# Artix7_SRAM.net
KiCad netlist of a schematic drawn in Altium Designer
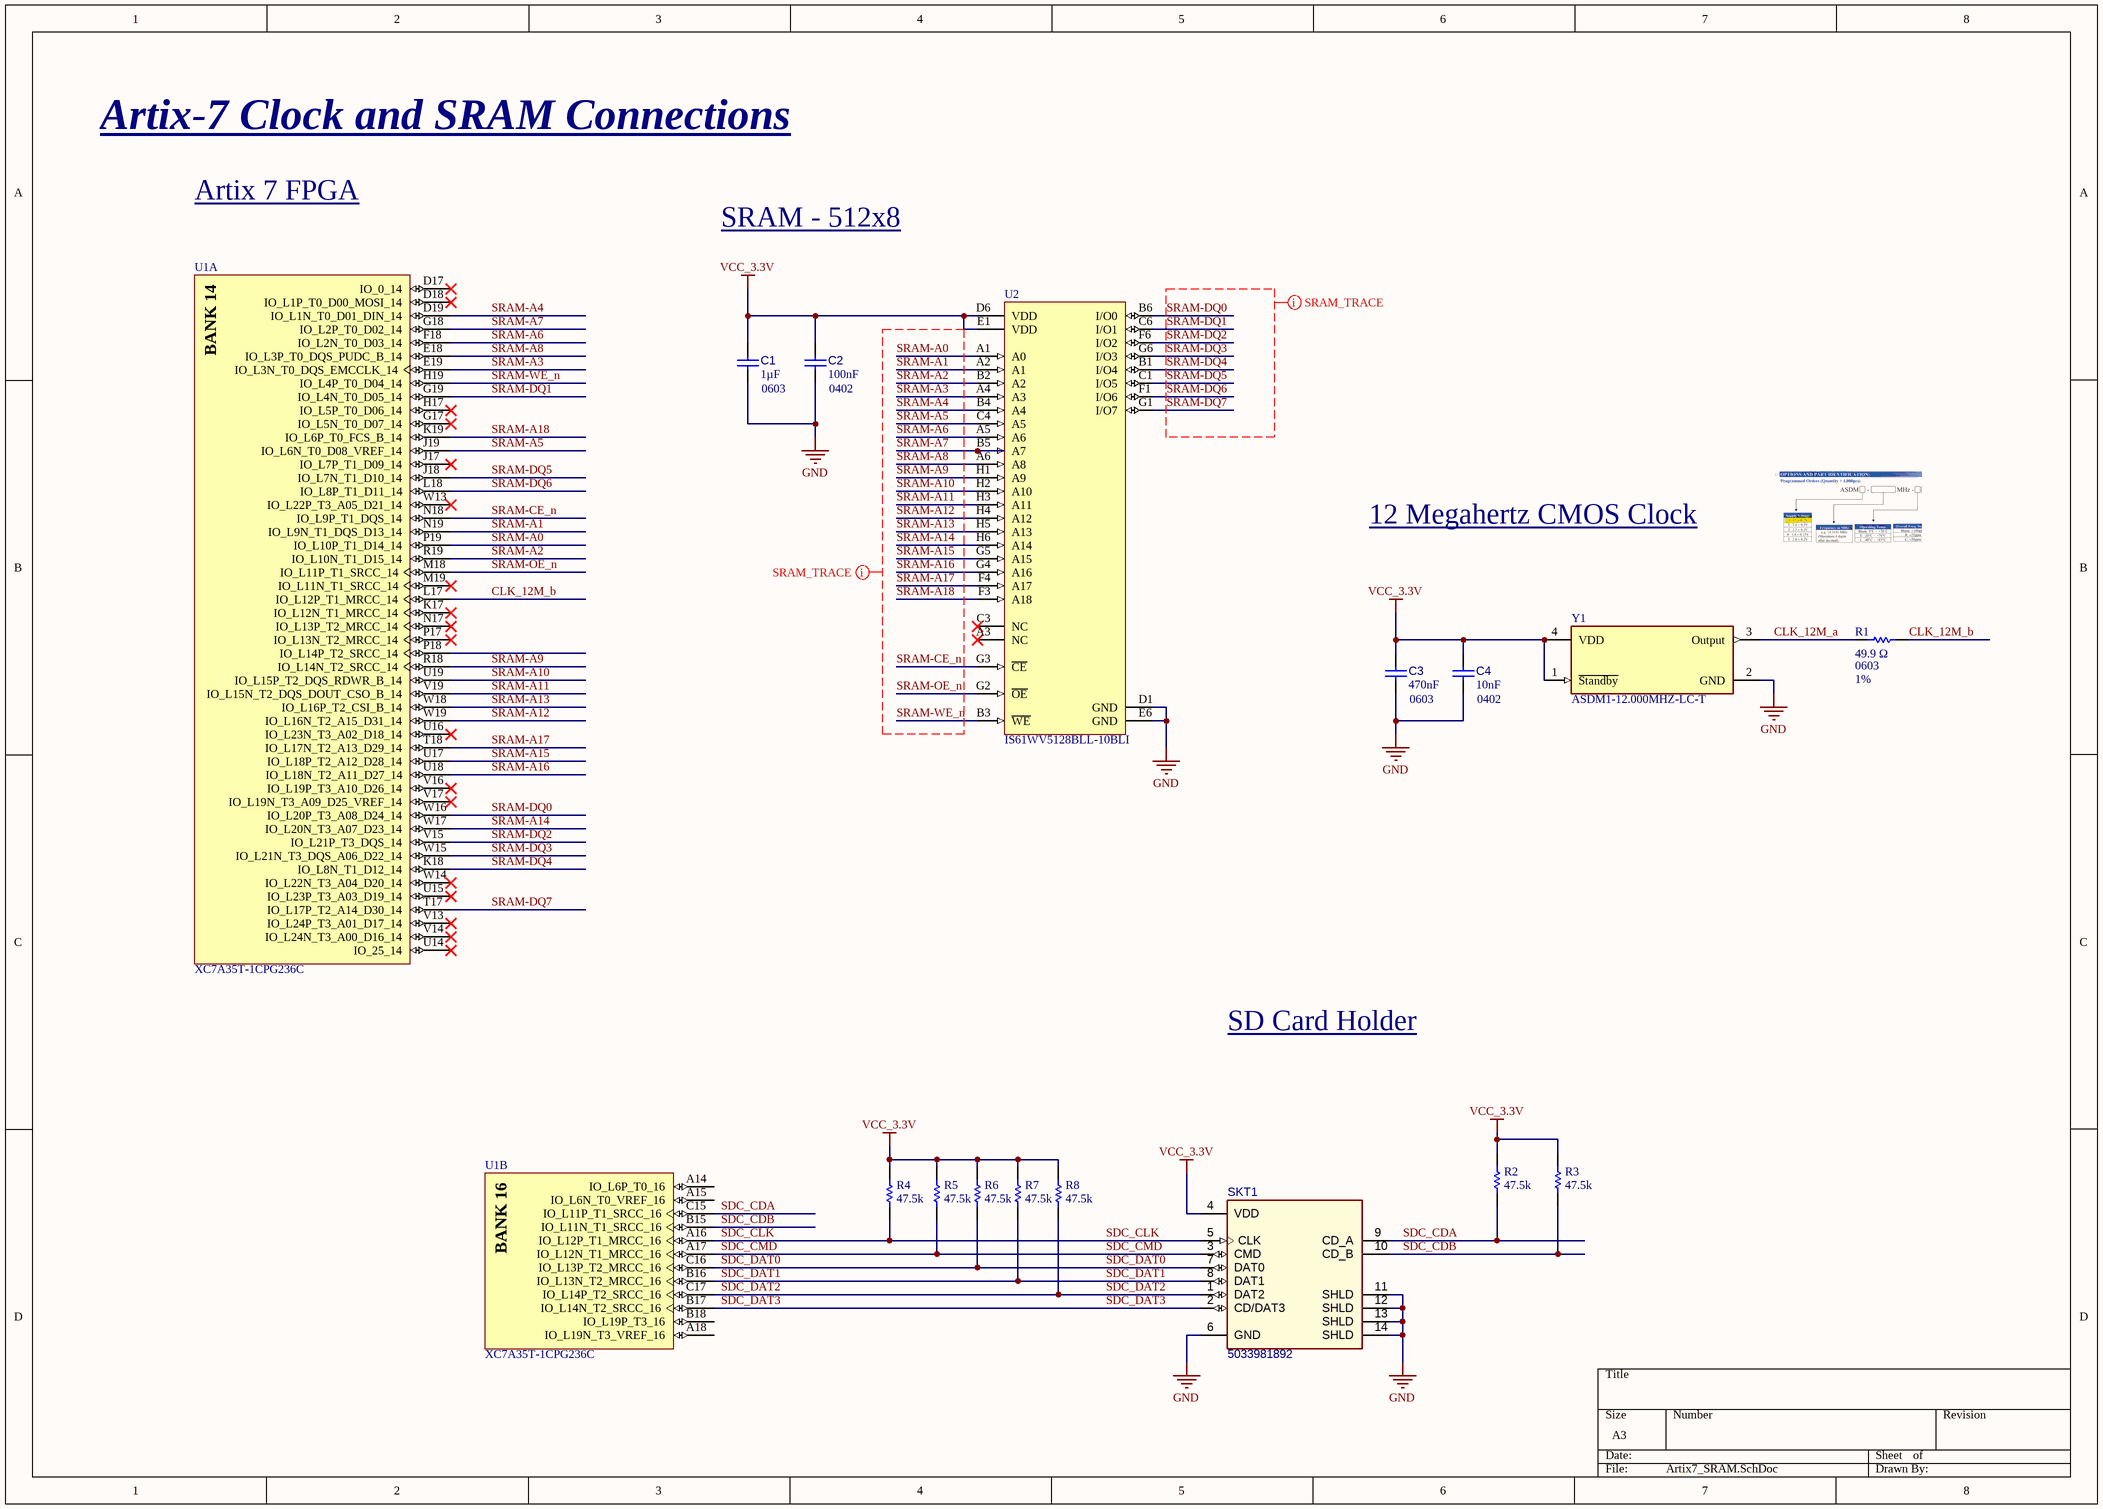
[diagram p0: Artix7_SRAM.SchDoc]

(export (version "E")
  (design (tool "Eeschema 10.0.6"))
  (components
    (comp (ref "C1")
      (value "1µF")
      (footprint "CAPC0603(1608)100_L")
      (description "Chip Capacitor, 1µF +/-0.1%, 25V, 0603, Thickness 1 mm")
      (fields
        (field (name "TOLERANCE") "20%")
        (field (name "CASE/PACKAGE") "0603")
        (field (name "Comment") "Capacitor 1µF +/-0.1% 25V 0603")
      )
      (libsource (lib "Personal Workspace") (part "CAP-NP-2"))
    )
    (comp (ref "C2")
      (value "100nF")
      (footprint "CAPC0402(1005)60_L")
      (description "Chip Capacitor, 100nF +/-20%, 25V, 0402, Thickness 0.6 mm")
      (fields
        (field (name "CASE/PACKAGE") "0402")
        (field (name "TOLERANCE") "10%")
        (field (name "Comment") "Capacitor 100nF +/-20% 25V 0402")
      )
      (libsource (lib "Personal Workspace") (part "CAP-NP-2"))
    )
    (comp (ref "C3")
      (value "470nF")
      (footprint "CAPC0603(1608)100_L")
      (description "Chip Capacitor, 470nF +/-20%, 25V, 0603, Thickness 1 mm")
      (fields
        (field (name "TOLERANCE") "10%")
        (field (name "CASE/PACKAGE") "0603")
        (field (name "Comment") "Capacitor 470nF +/-20% 25V 0603")
      )
      (libsource (lib "Personal Workspace") (part "CAP-NP-2"))
    )
    (comp (ref "C4")
      (value "10nF")
      (footprint "CAPC0402(1005)60_L")
      (description "Chip Capacitor, 10nF +/-20%, 50V, 0402, Thickness 0.6 mm")
      (fields
        (field (name "CASE/PACKAGE") "0402")
        (field (name "TOLERANCE") "5%")
        (field (name "Comment") "Capacitor 10nF +/-20% 50V 0402")
      )
      (libsource (lib "Personal Workspace") (part "CAP-NP-2"))
    )
    (comp (ref "R1")
      (value "49.9 Ω")
      (footprint "RESC1608X55X25NL10T15")
      (fields
        (field (name "PACKAGEREFERENCE") "0603")
        (field (name "TOLERANCE") "1%")
        (field (name "Comment") "RC0603FR-0749R9L")
      )
      (libsource (lib "Altium Content Vault") (part "RES-2"))
    )
    (comp (ref "R2")
      (value "47.5k")
      (footprint "RESC0402(1005)_L")
      (description "47K5 0.063W 1% 0402 (1005 Metric)  SMD")
      (fields (field (name "TOLERANCE") "1%") (field (name "POWER") "63mW"))
      (libsource (lib "Personal Workspace") (part "RES-2"))
    )
    (comp (ref "R3")
      (value "47.5k")
      (footprint "RESC0402(1005)_L")
      (description "47K5 0.063W 1% 0402 (1005 Metric)  SMD")
      (fields (field (name "TOLERANCE") "1%") (field (name "POWER") "63mW"))
      (libsource (lib "Personal Workspace") (part "RES-2"))
    )
    (comp (ref "R4")
      (value "47.5k")
      (footprint "RESC0402(1005)_L")
      (description "47K5 0.063W 1% 0402 (1005 Metric)  SMD")
      (fields (field (name "TOLERANCE") "1%") (field (name "POWER") "63mW"))
      (libsource (lib "Personal Workspace") (part "RES-2"))
    )
    (comp (ref "R5")
      (value "47.5k")
      (footprint "RESC0402(1005)_L")
      (description "47K5 0.063W 1% 0402 (1005 Metric)  SMD")
      (fields (field (name "TOLERANCE") "1%") (field (name "POWER") "63mW"))
      (libsource (lib "Personal Workspace") (part "RES-2"))
    )
    (comp (ref "R6")
      (value "47.5k")
      (footprint "RESC0402(1005)_L")
      (description "47K5 0.063W 1% 0402 (1005 Metric)  SMD")
      (fields (field (name "TOLERANCE") "1%") (field (name "POWER") "63mW"))
      (libsource (lib "Personal Workspace") (part "RES-2"))
    )
    (comp (ref "R7")
      (value "47.5k")
      (footprint "RESC0402(1005)_L")
      (description "47K5 0.063W 1% 0402 (1005 Metric)  SMD")
      (fields (field (name "TOLERANCE") "1%") (field (name "POWER") "63mW"))
      (libsource (lib "Personal Workspace") (part "RES-2"))
    )
    (comp (ref "R8")
      (value "47.5k")
      (footprint "RESC0402(1005)_L")
      (description "47K5 0.063W 1% 0402 (1005 Metric)  SMD")
      (fields (field (name "TOLERANCE") "1%") (field (name "POWER") "63mW"))
      (libsource (lib "Personal Workspace") (part "RES-2"))
    )
    (comp (ref "SKT1")
      (value "5033981892")
      (footprint "MOLX-5033981892_V")
      (libsource (lib "Personal Workspace") (part "CMP-00040-6"))
    )
    (comp (ref "U1")
      (value "XC7A35T-1CPG236C")
      (footprint "CPG236")
      (description "Artix-7 FPGA, 106 User I/Os, 2 GTP, 238-Ball BGA, Speed Grade 1, Commercial Grade, Pb-Free")
      (fields (field (name "MANUFACTURER") "Xilinx"))
      (libsource (lib "") (part "XLNX-XC7A35T-CPG236_1"))
    )
    (comp (ref "U2")
      (value "IS61WV5128BLL-10BLI")
      (footprint "FP-IS61WV5128BLL-10BLI-IPC_A")
      (libsource (lib "Altium Content Vault") (part "7547a2fdd47ed936ab9e56fa022b1f9"))
    )
    (comp (ref "Y1")
      (value "ASDM1-12.000MHZ-LC-T")
      (footprint "FP-ASDM-ASDMB-MFG")
      (description "MEMS Oscillator 12MHz ±50ppm LVCMOS 3.3V SMD 2.5x2mm")
      (libsource (lib "Altium Content Vault") (part "d1c68ac5f38726358044f3b7e06346c"))
    )
  )
  (nets
    (net (code "1") (name "/CLK_12M_a") (class "Default")
      (node (ref "R1") (pin "1") (pinfunction "1_1") (pintype "passive"))
      (node (ref "Y1") (pin "3") (pinfunction "Output_3") (pintype "output"))
    )
    (net (code "2") (name "/CLK_12M_b") (class "Default")
      (node (ref "R1") (pin "2") (pinfunction "2_2") (pintype "passive"))
      (node (ref "U1") (pin "L17") (pinfunction "IO_L12P_T1_MRCC_14_L17") (pintype "bidirectional"))
    )
    (net (code "3") (name "/SDC_CDA") (class "Default")
      (node (ref "R2") (pin "1") (pinfunction "1_1") (pintype "passive"))
      (node (ref "SKT1") (pin "9") (pinfunction "CD_A_9") (pintype "passive"))
      (node (ref "U1") (pin "C15") (pinfunction "IO_L11P_T1_SRCC_16_C15") (pintype "bidirectional"))
    )
    (net (code "4") (name "/SDC_CDB") (class "Default")
      (node (ref "R3") (pin "1") (pinfunction "1_1") (pintype "passive"))
      (node (ref "SKT1") (pin "10") (pinfunction "CD_B_10") (pintype "passive"))
      (node (ref "U1") (pin "B15") (pinfunction "IO_L11N_T1_SRCC_16_B15") (pintype "bidirectional"))
    )
    (net (code "5") (name "/SDC_CLK") (class "Default")
      (node (ref "R4") (pin "1") (pinfunction "1_1") (pintype "passive"))
      (node (ref "SKT1") (pin "5") (pinfunction "CLK_5") (pintype "input"))
      (node (ref "U1") (pin "A16") (pinfunction "IO_L12P_T1_MRCC_16_A16") (pintype "bidirectional"))
    )
    (net (code "6") (name "/SDC_CMD") (class "Default")
      (node (ref "R5") (pin "1") (pinfunction "1_1") (pintype "passive"))
      (node (ref "SKT1") (pin "3") (pinfunction "CMD_3") (pintype "bidirectional"))
      (node (ref "U1") (pin "A17") (pinfunction "IO_L12N_T1_MRCC_16_A17") (pintype "bidirectional"))
    )
    (net (code "7") (name "/SDC_DAT0") (class "Default")
      (node (ref "R6") (pin "1") (pinfunction "1_1") (pintype "passive"))
      (node (ref "SKT1") (pin "7") (pinfunction "DAT0_7") (pintype "bidirectional"))
      (node (ref "U1") (pin "C16") (pinfunction "IO_L13P_T2_MRCC_16_C16") (pintype "bidirectional"))
    )
    (net (code "8") (name "/SDC_DAT1") (class "Default")
      (node (ref "R7") (pin "1") (pinfunction "1_1") (pintype "passive"))
      (node (ref "SKT1") (pin "8") (pinfunction "DAT1_8") (pintype "bidirectional"))
      (node (ref "U1") (pin "B16") (pinfunction "IO_L13N_T2_MRCC_16_B16") (pintype "bidirectional"))
    )
    (net (code "9") (name "/SDC_DAT2") (class "Default")
      (node (ref "R8") (pin "1") (pinfunction "1_1") (pintype "passive"))
      (node (ref "SKT1") (pin "1") (pinfunction "DAT2_1") (pintype "bidirectional"))
      (node (ref "U1") (pin "C17") (pinfunction "IO_L14P_T2_SRCC_16_C17") (pintype "bidirectional"))
    )
    (net (code "10") (name "/SDC_DAT3") (class "Default")
      (node (ref "SKT1") (pin "2") (pinfunction "CD/DAT3_2") (pintype "bidirectional"))
      (node (ref "U1") (pin "B17") (pinfunction "IO_L14N_T2_SRCC_16_B17") (pintype "bidirectional"))
    )
    (net (code "11") (name "/SRAM-A0") (class "Default")
      (node (ref "U1") (pin "P19") (pinfunction "IO_L10P_T1_D14_14_P19") (pintype "bidirectional"))
      (node (ref "U2") (pin "A1") (pinfunction "A0_A1") (pintype "input"))
    )
    (net (code "12") (name "/SRAM-A1") (class "Default")
      (node (ref "U1") (pin "N19") (pinfunction "IO_L9N_T1_DQS_D13_14_N19") (pintype "bidirectional"))
      (node (ref "U2") (pin "A2") (pinfunction "A1_A2") (pintype "input"))
    )
    (net (code "13") (name "/SRAM-A2") (class "Default")
      (node (ref "U1") (pin "R19") (pinfunction "IO_L10N_T1_D15_14_R19") (pintype "bidirectional"))
      (node (ref "U2") (pin "B2") (pinfunction "A2_B2") (pintype "input"))
    )
    (net (code "14") (name "/SRAM-A3") (class "Default")
      (node (ref "U1") (pin "E19") (pinfunction "IO_L3N_T0_DQS_EMCCLK_14_E19") (pintype "bidirectional"))
      (node (ref "U2") (pin "A4") (pinfunction "A3_A4") (pintype "input"))
    )
    (net (code "15") (name "/SRAM-A4") (class "Default")
      (node (ref "U1") (pin "D19") (pinfunction "IO_L1N_T0_D01_DIN_14_D19") (pintype "bidirectional"))
      (node (ref "U2") (pin "B4") (pinfunction "A4_B4") (pintype "input"))
    )
    (net (code "16") (name "/SRAM-A5") (class "Default")
      (node (ref "U1") (pin "J19") (pinfunction "IO_L6N_T0_D08_VREF_14_J19") (pintype "bidirectional"))
      (node (ref "U2") (pin "C4") (pinfunction "A5_C4") (pintype "input"))
    )
    (net (code "17") (name "/SRAM-A6") (class "Default")
      (node (ref "U1") (pin "F18") (pinfunction "IO_L2N_T0_D03_14_F18") (pintype "bidirectional"))
      (node (ref "U2") (pin "A5") (pinfunction "A6_A5") (pintype "input"))
    )
    (net (code "18") (name "/SRAM-A7") (class "Default")
      (node (ref "U1") (pin "G18") (pinfunction "IO_L2P_T0_D02_14_G18") (pintype "bidirectional"))
      (node (ref "U2") (pin "B5") (pinfunction "A7_B5") (pintype "input"))
    )
    (net (code "19") (name "/SRAM-A8") (class "Default")
      (node (ref "U1") (pin "E18") (pinfunction "IO_L3P_T0_DQS_PUDC_B_14_E18") (pintype "bidirectional"))
      (node (ref "U2") (pin "A6") (pinfunction "A8_A6") (pintype "input"))
    )
    (net (code "20") (name "/SRAM-A9") (class "Default")
      (node (ref "U1") (pin "R18") (pinfunction "IO_L14N_T2_SRCC_14_R18") (pintype "bidirectional"))
      (node (ref "U2") (pin "H1") (pinfunction "A9_H1") (pintype "input"))
    )
    (net (code "21") (name "/SRAM-A10") (class "Default")
      (node (ref "U1") (pin "U19") (pinfunction "IO_L15P_T2_DQS_RDWR_B_14_U19") (pintype "bidirectional"))
      (node (ref "U2") (pin "H2") (pinfunction "A10_H2") (pintype "input"))
    )
    (net (code "22") (name "/SRAM-A11") (class "Default")
      (node (ref "U1") (pin "V19") (pinfunction "IO_L15N_T2_DQS_DOUT_CSO_B_14_V19") (pintype "bidirectional"))
      (node (ref "U2") (pin "H3") (pinfunction "A11_H3") (pintype "input"))
    )
    (net (code "23") (name "/SRAM-A12") (class "Default")
      (node (ref "U1") (pin "W19") (pinfunction "IO_L16N_T2_A15_D31_14_W19") (pintype "bidirectional"))
      (node (ref "U2") (pin "H4") (pinfunction "A12_H4") (pintype "input"))
    )
    (net (code "24") (name "/SRAM-A13") (class "Default")
      (node (ref "U1") (pin "W18") (pinfunction "IO_L16P_T2_CSI_B_14_W18") (pintype "bidirectional"))
      (node (ref "U2") (pin "H5") (pinfunction "A13_H5") (pintype "input"))
    )
    (net (code "25") (name "/SRAM-A14") (class "Default")
      (node (ref "U1") (pin "W17") (pinfunction "IO_L20N_T3_A07_D23_14_W17") (pintype "bidirectional"))
      (node (ref "U2") (pin "H6") (pinfunction "A14_H6") (pintype "input"))
    )
    (net (code "26") (name "/SRAM-A15") (class "Default")
      (node (ref "U1") (pin "U17") (pinfunction "IO_L18P_T2_A12_D28_14_U17") (pintype "bidirectional"))
      (node (ref "U2") (pin "G5") (pinfunction "A15_G5") (pintype "input"))
    )
    (net (code "27") (name "/SRAM-A16") (class "Default")
      (node (ref "U1") (pin "U18") (pinfunction "IO_L18N_T2_A11_D27_14_U18") (pintype "bidirectional"))
      (node (ref "U2") (pin "G4") (pinfunction "A16_G4") (pintype "input"))
    )
    (net (code "28") (name "/SRAM-A17") (class "Default")
      (node (ref "U1") (pin "T18") (pinfunction "IO_L17N_T2_A13_D29_14_T18") (pintype "bidirectional"))
      (node (ref "U2") (pin "F4") (pinfunction "A17_F4") (pintype "input"))
    )
    (net (code "29") (name "/SRAM-A18") (class "Default")
      (node (ref "U1") (pin "K19") (pinfunction "IO_L6P_T0_FCS_B_14_K19") (pintype "bidirectional"))
      (node (ref "U2") (pin "F3") (pinfunction "A18_F3") (pintype "input"))
    )
    (net (code "30") (name "/SRAM-CE_n") (class "Default")
      (node (ref "U1") (pin "N18") (pinfunction "IO_L9P_T1_DQS_14_N18") (pintype "bidirectional"))
      (node (ref "U2") (pin "G3") (pinfunction "~{CE}_G3") (pintype "input"))
    )
    (net (code "31") (name "/SRAM-DQ0") (class "Default")
      (node (ref "U1") (pin "W16") (pinfunction "IO_L20P_T3_A08_D24_14_W16") (pintype "bidirectional"))
      (node (ref "U2") (pin "B6") (pinfunction "I/O0_B6") (pintype "bidirectional"))
    )
    (net (code "32") (name "/SRAM-DQ1") (class "Default")
      (node (ref "U1") (pin "G19") (pinfunction "IO_L4N_T0_D05_14_G19") (pintype "bidirectional"))
      (node (ref "U2") (pin "C6") (pinfunction "I/O1_C6") (pintype "bidirectional"))
    )
    (net (code "33") (name "/SRAM-DQ2") (class "Default")
      (node (ref "U1") (pin "V15") (pinfunction "IO_L21P_T3_DQS_14_V15") (pintype "bidirectional"))
      (node (ref "U2") (pin "F6") (pinfunction "I/O2_F6") (pintype "bidirectional"))
    )
    (net (code "34") (name "/SRAM-DQ3") (class "Default")
      (node (ref "U1") (pin "W15") (pinfunction "IO_L21N_T3_DQS_A06_D22_14_W15") (pintype "bidirectional"))
      (node (ref "U2") (pin "G6") (pinfunction "I/O3_G6") (pintype "bidirectional"))
    )
    (net (code "35") (name "/SRAM-DQ4") (class "Default")
      (node (ref "U1") (pin "K18") (pinfunction "IO_L8N_T1_D12_14_K18") (pintype "bidirectional"))
      (node (ref "U2") (pin "B1") (pinfunction "I/O4_B1") (pintype "bidirectional"))
    )
    (net (code "36") (name "/SRAM-DQ5") (class "Default")
      (node (ref "U1") (pin "J18") (pinfunction "IO_L7N_T1_D10_14_J18") (pintype "bidirectional"))
      (node (ref "U2") (pin "C1") (pinfunction "I/O5_C1") (pintype "bidirectional"))
    )
    (net (code "37") (name "/SRAM-DQ6") (class "Default")
      (node (ref "U1") (pin "L18") (pinfunction "IO_L8P_T1_D11_14_L18") (pintype "bidirectional"))
      (node (ref "U2") (pin "F1") (pinfunction "I/O6_F1") (pintype "bidirectional"))
    )
    (net (code "38") (name "/SRAM-DQ7") (class "Default")
      (node (ref "U1") (pin "T17") (pinfunction "IO_L17P_T2_A14_D30_14_T17") (pintype "bidirectional"))
      (node (ref "U2") (pin "G1") (pinfunction "I/O7_G1") (pintype "bidirectional"))
    )
    (net (code "39") (name "/SRAM-OE_n") (class "Default")
      (node (ref "U1") (pin "M18") (pinfunction "IO_L11P_T1_SRCC_14_M18") (pintype "bidirectional"))
      (node (ref "U2") (pin "G2") (pinfunction "~{OE}_G2") (pintype "input"))
    )
    (net (code "40") (name "/SRAM-WE_n") (class "Default")
      (node (ref "U1") (pin "H19") (pinfunction "IO_L4P_T0_D04_14_H19") (pintype "bidirectional"))
      (node (ref "U2") (pin "B3") (pinfunction "~{WE}_B3") (pintype "input"))
    )
    (net (code "41") (name "GND") (class "Default")
      (node (ref "C1") (pin "1") (pinfunction "1_1") (pintype "passive"))
      (node (ref "C2") (pin "1") (pinfunction "1_1") (pintype "passive"))
      (node (ref "C3") (pin "1") (pinfunction "1_1") (pintype "passive"))
      (node (ref "C4") (pin "2") (pinfunction "2_2") (pintype "passive"))
      (node (ref "SKT1") (pin "11") (pinfunction "SHLD_11") (pintype "passive"))
      (node (ref "SKT1") (pin "12") (pinfunction "SHLD_12") (pintype "passive"))
      (node (ref "SKT1") (pin "13") (pinfunction "SHLD_13") (pintype "passive"))
      (node (ref "SKT1") (pin "14") (pinfunction "SHLD_14") (pintype "passive"))
      (node (ref "SKT1") (pin "6") (pinfunction "GND_6") (pintype "passive"))
      (node (ref "U2") (pin "D1") (pinfunction "GND_D1") (pintype "power_in"))
      (node (ref "U2") (pin "E6") (pinfunction "GND_E6") (pintype "power_in"))
      (node (ref "Y1") (pin "2") (pinfunction "GND_2") (pintype "power_in"))
    )
    (net (code "42") (name "VCC_3.3V") (class "Default")
      (node (ref "C1") (pin "2") (pinfunction "2_2") (pintype "passive"))
      (node (ref "C2") (pin "2") (pinfunction "2_2") (pintype "passive"))
      (node (ref "C3") (pin "2") (pinfunction "2_2") (pintype "passive"))
      (node (ref "C4") (pin "1") (pinfunction "1_1") (pintype "passive"))
      (node (ref "R2") (pin "2") (pinfunction "2_2") (pintype "passive"))
      (node (ref "R3") (pin "2") (pinfunction "2_2") (pintype "passive"))
      (node (ref "R4") (pin "2") (pinfunction "2_2") (pintype "passive"))
      (node (ref "R5") (pin "2") (pinfunction "2_2") (pintype "passive"))
      (node (ref "R6") (pin "2") (pinfunction "2_2") (pintype "passive"))
      (node (ref "R7") (pin "2") (pinfunction "2_2") (pintype "passive"))
      (node (ref "R8") (pin "2") (pinfunction "2_2") (pintype "passive"))
      (node (ref "SKT1") (pin "4") (pinfunction "VDD_4") (pintype "power_in"))
      (node (ref "U2") (pin "D6") (pinfunction "VDD_D6") (pintype "power_in"))
      (node (ref "U2") (pin "E1") (pinfunction "VDD_E1") (pintype "power_in"))
      (node (ref "Y1") (pin "1") (pinfunction "~{Standby}_1") (pintype "input"))
      (node (ref "Y1") (pin "4") (pinfunction "VDD_4") (pintype "power_in"))
    )
    (net (code "43") (name "unconnected-(U1A-IO_0_14-PadD17)") (class "Default")
      (node (ref "U1") (pin "D17") (pinfunction "IO_0_14_D17") (pintype "bidirectional+no_connect"))
    )
    (net (code "44") (name "unconnected-(U1A-IO_25_14-PadU14)") (class "Default")
      (node (ref "U1") (pin "U14") (pinfunction "IO_25_14_U14") (pintype "bidirectional+no_connect"))
    )
    (net (code "45") (name "unconnected-(U1A-IO_L1P_T0_D00_MOSI_14-PadD18)") (class "Default")
      (node (ref "U1") (pin "D18") (pinfunction "IO_L1P_T0_D00_MOSI_14_D18") (pintype "bidirectional+no_connect"))
    )
    (net (code "46") (name "unconnected-(U1A-IO_L5N_T0_D07_14-PadG17)") (class "Default")
      (node (ref "U1") (pin "G17") (pinfunction "IO_L5N_T0_D07_14_G17") (pintype "bidirectional+no_connect"))
    )
    (net (code "47") (name "unconnected-(U1A-IO_L5P_T0_D06_14-PadH17)") (class "Default")
      (node (ref "U1") (pin "H17") (pinfunction "IO_L5P_T0_D06_14_H17") (pintype "bidirectional+no_connect"))
    )
    (net (code "48") (name "unconnected-(U1A-IO_L7P_T1_D09_14-PadJ17)") (class "Default")
      (node (ref "U1") (pin "J17") (pinfunction "IO_L7P_T1_D09_14_J17") (pintype "bidirectional+no_connect"))
    )
    (net (code "49") (name "unconnected-(U1A-IO_L11N_T1_SRCC_14-PadM19)") (class "Default")
      (node (ref "U1") (pin "M19") (pinfunction "IO_L11N_T1_SRCC_14_M19") (pintype "bidirectional+no_connect"))
    )
    (net (code "50") (name "unconnected-(U1A-IO_L12N_T1_MRCC_14-PadK17)") (class "Default")
      (node (ref "U1") (pin "K17") (pinfunction "IO_L12N_T1_MRCC_14_K17") (pintype "bidirectional+no_connect"))
    )
    (net (code "51") (name "unconnected-(U1A-IO_L13N_T2_MRCC_14-PadP17)") (class "Default")
      (node (ref "U1") (pin "P17") (pinfunction "IO_L13N_T2_MRCC_14_P17") (pintype "bidirectional+no_connect"))
    )
    (net (code "52") (name "unconnected-(U1A-IO_L13P_T2_MRCC_14-PadN17)") (class "Default")
      (node (ref "U1") (pin "N17") (pinfunction "IO_L13P_T2_MRCC_14_N17") (pintype "bidirectional+no_connect"))
    )
    (net (code "53") (name "unconnected-(U1A-IO_L14P_T2_SRCC_14-PadP18)") (class "Default")
      (node (ref "U1") (pin "P18") (pinfunction "IO_L14P_T2_SRCC_14_P18") (pintype "bidirectional"))
    )
    (net (code "54") (name "unconnected-(U1A-IO_L19N_T3_A09_D25_VREF_14-PadV17)") (class "Default")
      (node (ref "U1") (pin "V17") (pinfunction "IO_L19N_T3_A09_D25_VREF_14_V17") (pintype "bidirectional+no_connect"))
    )
    (net (code "55") (name "unconnected-(U1A-IO_L19P_T3_A10_D26_14-PadV16)") (class "Default")
      (node (ref "U1") (pin "V16") (pinfunction "IO_L19P_T3_A10_D26_14_V16") (pintype "bidirectional+no_connect"))
    )
    (net (code "56") (name "unconnected-(U1A-IO_L22N_T3_A04_D20_14-PadW14)") (class "Default")
      (node (ref "U1") (pin "W14") (pinfunction "IO_L22N_T3_A04_D20_14_W14") (pintype "bidirectional+no_connect"))
    )
    (net (code "57") (name "unconnected-(U1A-IO_L22P_T3_A05_D21_14-PadW13)") (class "Default")
      (node (ref "U1") (pin "W13") (pinfunction "IO_L22P_T3_A05_D21_14_W13") (pintype "bidirectional+no_connect"))
    )
    (net (code "58") (name "unconnected-(U1A-IO_L23N_T3_A02_D18_14-PadU16)") (class "Default")
      (node (ref "U1") (pin "U16") (pinfunction "IO_L23N_T3_A02_D18_14_U16") (pintype "bidirectional+no_connect"))
    )
    (net (code "59") (name "unconnected-(U1A-IO_L23P_T3_A03_D19_14-PadU15)") (class "Default")
      (node (ref "U1") (pin "U15") (pinfunction "IO_L23P_T3_A03_D19_14_U15") (pintype "bidirectional+no_connect"))
    )
    (net (code "60") (name "unconnected-(U1A-IO_L24N_T3_A00_D16_14-PadV14)") (class "Default")
      (node (ref "U1") (pin "V14") (pinfunction "IO_L24N_T3_A00_D16_14_V14") (pintype "bidirectional+no_connect"))
    )
    (net (code "61") (name "unconnected-(U1A-IO_L24P_T3_A01_D17_14-PadV13)") (class "Default")
      (node (ref "U1") (pin "V13") (pinfunction "IO_L24P_T3_A01_D17_14_V13") (pintype "bidirectional+no_connect"))
    )
    (net (code "62") (name "unconnected-(U1B-IO_L6N_T0_VREF_16-PadA15)") (class "Default")
      (node (ref "U1") (pin "A15") (pinfunction "IO_L6N_T0_VREF_16_A15") (pintype "bidirectional"))
    )
    (net (code "63") (name "unconnected-(U1B-IO_L6P_T0_16-PadA14)") (class "Default")
      (node (ref "U1") (pin "A14") (pinfunction "IO_L6P_T0_16_A14") (pintype "bidirectional"))
    )
    (net (code "64") (name "unconnected-(U1B-IO_L19N_T3_VREF_16-PadA18)") (class "Default")
      (node (ref "U1") (pin "A18") (pinfunction "IO_L19N_T3_VREF_16_A18") (pintype "bidirectional"))
    )
    (net (code "65") (name "unconnected-(U1B-IO_L19P_T3_16-PadB18)") (class "Default")
      (node (ref "U1") (pin "B18") (pinfunction "IO_L19P_T3_16_B18") (pintype "bidirectional"))
    )
    (net (code "66") (name "unconnected-(U2-NC-PadA3)") (class "Default")
      (node (ref "U2") (pin "A3") (pinfunction "NC_A3") (pintype "passive+no_connect"))
    )
    (net (code "67") (name "unconnected-(U2-NC-PadC3)") (class "Default")
      (node (ref "U2") (pin "C3") (pinfunction "NC_C3") (pintype "passive+no_connect"))
    )
  )
)
